# SignalsInOut.net
KiCad netlist of a schematic drawn in Altium Designer
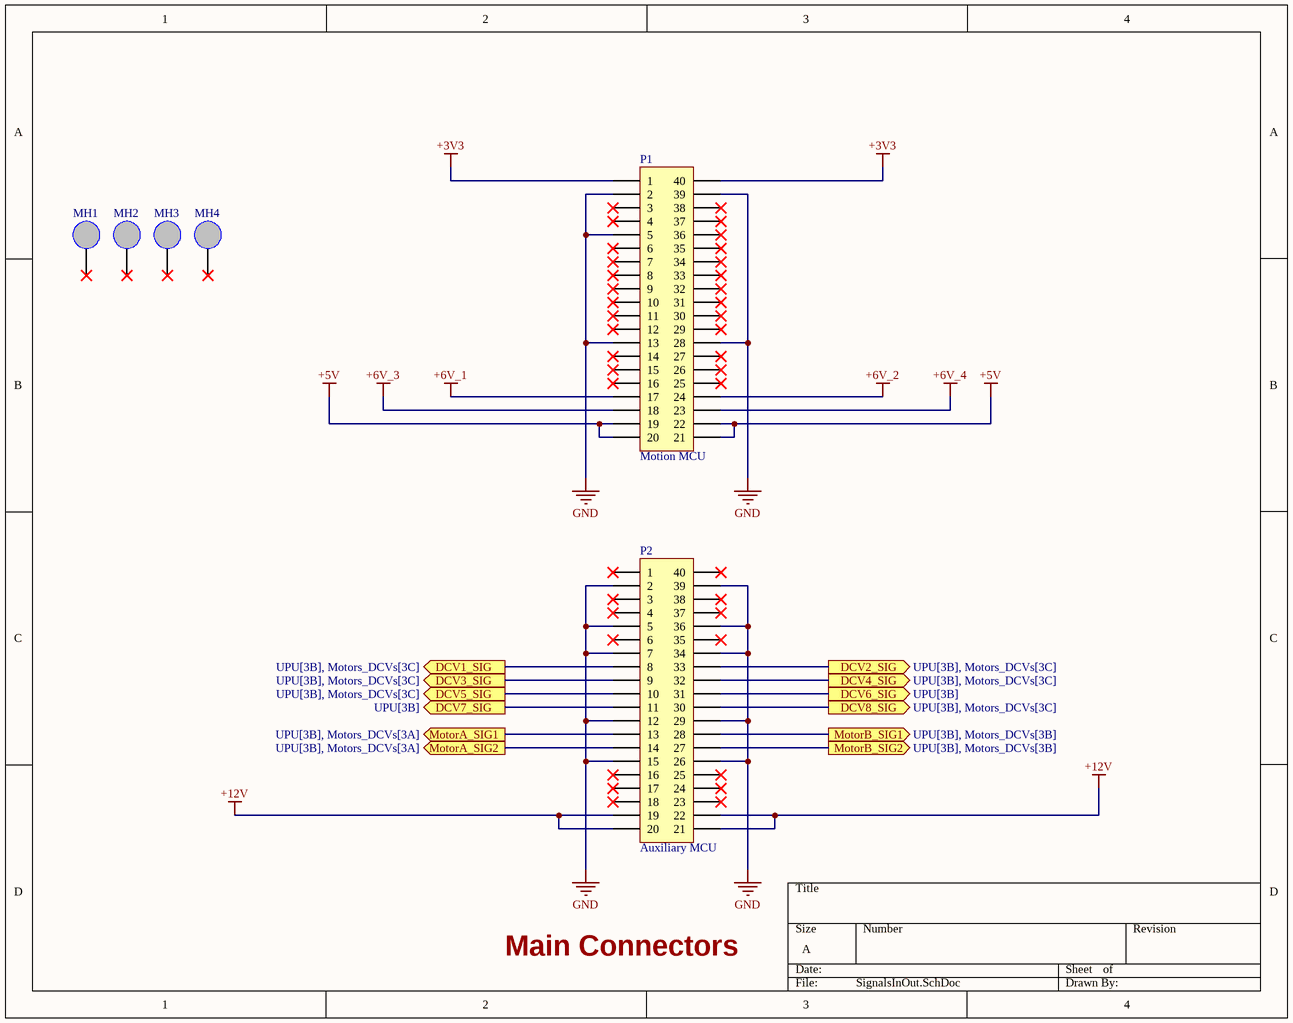
[diagram p0: SignalsInOut.SchDoc]

(export (version "E")
  (design (tool "Eeschema 10.0.6"))
  (components
    (comp (ref "MH1")
      (value "Mounting Hole 3.5mm")
      (footprint "Connector Mounting hole TH 3.5mm")
      (libsource (lib "Bypass, Testpoint and Holes") (part "Mounting Hole 3.5mm"))
    )
    (comp (ref "MH2")
      (value "Mounting Hole 3.5mm")
      (footprint "Connector Mounting hole TH 3.5mm")
      (libsource (lib "Bypass, Testpoint and Holes") (part "Mounting Hole 3.5mm"))
    )
    (comp (ref "MH3")
      (value "Mounting Hole 3.5mm")
      (footprint "Connector Mounting hole TH 3.5mm")
      (libsource (lib "Bypass, Testpoint and Holes") (part "Mounting Hole 3.5mm"))
    )
    (comp (ref "MH4")
      (value "Mounting Hole 3.5mm")
      (footprint "Connector Mounting hole TH 3.5mm")
      (libsource (lib "Bypass, Testpoint and Holes") (part "Mounting Hole 3.5mm"))
    )
    (comp (ref "P1")
      (value "Motion MCU")
      (footprint "Header F 2.54_2X20")
      (description "Header_2X20")
      (libsource (lib "Signal connectors") (part "Connector Pinheader 2x20"))
    )
    (comp (ref "P2")
      (value "Auxiliary MCU")
      (footprint "Header F 2.54_2X20")
      (description "Header_2X20")
      (libsource (lib "Signal connectors") (part "Connector Pinheader 2x20"))
    )
  )
  (nets
    (net (code "1") (name "+3V3") (class "Default")
      (node (ref "P1") (pin "1") (pinfunction "1_1") (pintype "tri_state"))
      (node (ref "P1") (pin "40") (pinfunction "40_40") (pintype "tri_state"))
    )
    (net (code "2") (name "+5V") (class "Default")
      (node (ref "P1") (pin "19") (pinfunction "19_19") (pintype "tri_state"))
      (node (ref "P1") (pin "20") (pinfunction "20_20") (pintype "tri_state"))
      (node (ref "P1") (pin "21") (pinfunction "21_21") (pintype "tri_state"))
      (node (ref "P1") (pin "22") (pinfunction "22_22") (pintype "tri_state"))
    )
    (net (code "3") (name "+6V_1") (class "Default")
      (node (ref "P1") (pin "17") (pinfunction "17_17") (pintype "tri_state"))
    )
    (net (code "4") (name "+6V_2") (class "Default")
      (node (ref "P1") (pin "24") (pinfunction "24_24") (pintype "tri_state"))
    )
    (net (code "5") (name "+6V_3") (class "Default")
      (node (ref "P1") (pin "18") (pinfunction "18_18") (pintype "tri_state"))
    )
    (net (code "6") (name "+6V_4") (class "Default")
      (node (ref "P1") (pin "23") (pinfunction "23_23") (pintype "tri_state"))
    )
    (net (code "7") (name "+12V") (class "Default")
      (node (ref "P2") (pin "19") (pinfunction "19_19") (pintype "tri_state"))
      (node (ref "P2") (pin "20") (pinfunction "20_20") (pintype "tri_state"))
      (node (ref "P2") (pin "21") (pinfunction "21_21") (pintype "tri_state"))
      (node (ref "P2") (pin "22") (pinfunction "22_22") (pintype "tri_state"))
    )
    (net (code "8") (name "/DCV1_SIG") (class "Default")
      (node (ref "P2") (pin "8") (pinfunction "8_8") (pintype "tri_state"))
    )
    (net (code "9") (name "/DCV2_SIG") (class "Default")
      (node (ref "P2") (pin "33") (pinfunction "33_33") (pintype "tri_state"))
    )
    (net (code "10") (name "/DCV3_SIG") (class "Default")
      (node (ref "P2") (pin "9") (pinfunction "9_9") (pintype "tri_state"))
    )
    (net (code "11") (name "/DCV4_SIG") (class "Default")
      (node (ref "P2") (pin "32") (pinfunction "32_32") (pintype "tri_state"))
    )
    (net (code "12") (name "/DCV5_SIG") (class "Default")
      (node (ref "P2") (pin "10") (pinfunction "10_10") (pintype "tri_state"))
    )
    (net (code "13") (name "/DCV6_SIG") (class "Default")
      (node (ref "P2") (pin "31") (pinfunction "31_31") (pintype "tri_state"))
    )
    (net (code "14") (name "/DCV7_SIG") (class "Default")
      (node (ref "P2") (pin "11") (pinfunction "11_11") (pintype "tri_state"))
    )
    (net (code "15") (name "/DCV8_SIG") (class "Default")
      (node (ref "P2") (pin "30") (pinfunction "30_30") (pintype "tri_state"))
    )
    (net (code "16") (name "/MotorA_SIG1") (class "Default")
      (node (ref "P2") (pin "13") (pinfunction "13_13") (pintype "tri_state"))
    )
    (net (code "17") (name "/MotorA_SIG2") (class "Default")
      (node (ref "P2") (pin "14") (pinfunction "14_14") (pintype "tri_state"))
    )
    (net (code "18") (name "/MotorB_SIG1") (class "Default")
      (node (ref "P2") (pin "28") (pinfunction "28_28") (pintype "tri_state"))
    )
    (net (code "19") (name "/MotorB_SIG2") (class "Default")
      (node (ref "P2") (pin "27") (pinfunction "27_27") (pintype "tri_state"))
    )
    (net (code "20") (name "GND") (class "Default")
      (node (ref "P1") (pin "13") (pinfunction "13_13") (pintype "tri_state"))
      (node (ref "P1") (pin "2") (pinfunction "2_2") (pintype "tri_state"))
      (node (ref "P1") (pin "28") (pinfunction "28_28") (pintype "tri_state"))
      (node (ref "P1") (pin "39") (pinfunction "39_39") (pintype "tri_state"))
      (node (ref "P1") (pin "5") (pinfunction "5_5") (pintype "tri_state"))
      (node (ref "P2") (pin "12") (pinfunction "12_12") (pintype "tri_state"))
      (node (ref "P2") (pin "15") (pinfunction "15_15") (pintype "tri_state"))
      (node (ref "P2") (pin "2") (pinfunction "2_2") (pintype "tri_state"))
      (node (ref "P2") (pin "26") (pinfunction "26_26") (pintype "tri_state"))
      (node (ref "P2") (pin "29") (pinfunction "29_29") (pintype "tri_state"))
      (node (ref "P2") (pin "34") (pinfunction "34_34") (pintype "tri_state"))
      (node (ref "P2") (pin "36") (pinfunction "36_36") (pintype "tri_state"))
      (node (ref "P2") (pin "39") (pinfunction "39_39") (pintype "tri_state"))
      (node (ref "P2") (pin "5") (pinfunction "5_5") (pintype "tri_state"))
      (node (ref "P2") (pin "7") (pinfunction "7_7") (pintype "tri_state"))
    )
    (net (code "21") (name "unconnected-(MH1-Pad1)") (class "Default")
      (node (ref "MH1") (pin "1") (pinfunction "1_1") (pintype "passive+no_connect"))
    )
    (net (code "22") (name "unconnected-(MH2-Pad1)") (class "Default")
      (node (ref "MH2") (pin "1") (pinfunction "1_1") (pintype "passive+no_connect"))
    )
    (net (code "23") (name "unconnected-(MH3-Pad1)") (class "Default")
      (node (ref "MH3") (pin "1") (pinfunction "1_1") (pintype "passive+no_connect"))
    )
    (net (code "24") (name "unconnected-(MH4-Pad1)") (class "Default")
      (node (ref "MH4") (pin "1") (pinfunction "1_1") (pintype "passive+no_connect"))
    )
    (net (code "25") (name "unconnected-(P1-Pad3)") (class "Default")
      (node (ref "P1") (pin "3") (pinfunction "3_3") (pintype "tri_state+no_connect"))
    )
    (net (code "26") (name "unconnected-(P1-Pad4)") (class "Default")
      (node (ref "P1") (pin "4") (pinfunction "4_4") (pintype "tri_state+no_connect"))
    )
    (net (code "27") (name "unconnected-(P1-Pad6)") (class "Default")
      (node (ref "P1") (pin "6") (pinfunction "6_6") (pintype "tri_state+no_connect"))
    )
    (net (code "28") (name "unconnected-(P1-Pad7)") (class "Default")
      (node (ref "P1") (pin "7") (pinfunction "7_7") (pintype "tri_state+no_connect"))
    )
    (net (code "29") (name "unconnected-(P1-Pad8)") (class "Default")
      (node (ref "P1") (pin "8") (pinfunction "8_8") (pintype "tri_state+no_connect"))
    )
    (net (code "30") (name "unconnected-(P1-Pad9)") (class "Default")
      (node (ref "P1") (pin "9") (pinfunction "9_9") (pintype "tri_state+no_connect"))
    )
    (net (code "31") (name "unconnected-(P1-Pad10)") (class "Default")
      (node (ref "P1") (pin "10") (pinfunction "10_10") (pintype "tri_state+no_connect"))
    )
    (net (code "32") (name "unconnected-(P1-Pad11)") (class "Default")
      (node (ref "P1") (pin "11") (pinfunction "11_11") (pintype "tri_state+no_connect"))
    )
    (net (code "33") (name "unconnected-(P1-Pad12)") (class "Default")
      (node (ref "P1") (pin "12") (pinfunction "12_12") (pintype "tri_state+no_connect"))
    )
    (net (code "34") (name "unconnected-(P1-Pad14)") (class "Default")
      (node (ref "P1") (pin "14") (pinfunction "14_14") (pintype "tri_state+no_connect"))
    )
    (net (code "35") (name "unconnected-(P1-Pad15)") (class "Default")
      (node (ref "P1") (pin "15") (pinfunction "15_15") (pintype "tri_state+no_connect"))
    )
    (net (code "36") (name "unconnected-(P1-Pad16)") (class "Default")
      (node (ref "P1") (pin "16") (pinfunction "16_16") (pintype "tri_state+no_connect"))
    )
    (net (code "37") (name "unconnected-(P1-Pad25)") (class "Default")
      (node (ref "P1") (pin "25") (pinfunction "25_25") (pintype "tri_state+no_connect"))
    )
    (net (code "38") (name "unconnected-(P1-Pad26)") (class "Default")
      (node (ref "P1") (pin "26") (pinfunction "26_26") (pintype "tri_state+no_connect"))
    )
    (net (code "39") (name "unconnected-(P1-Pad27)") (class "Default")
      (node (ref "P1") (pin "27") (pinfunction "27_27") (pintype "tri_state+no_connect"))
    )
    (net (code "40") (name "unconnected-(P1-Pad29)") (class "Default")
      (node (ref "P1") (pin "29") (pinfunction "29_29") (pintype "tri_state+no_connect"))
    )
    (net (code "41") (name "unconnected-(P1-Pad30)") (class "Default")
      (node (ref "P1") (pin "30") (pinfunction "30_30") (pintype "tri_state+no_connect"))
    )
    (net (code "42") (name "unconnected-(P1-Pad31)") (class "Default")
      (node (ref "P1") (pin "31") (pinfunction "31_31") (pintype "tri_state+no_connect"))
    )
    (net (code "43") (name "unconnected-(P1-Pad32)") (class "Default")
      (node (ref "P1") (pin "32") (pinfunction "32_32") (pintype "tri_state+no_connect"))
    )
    (net (code "44") (name "unconnected-(P1-Pad33)") (class "Default")
      (node (ref "P1") (pin "33") (pinfunction "33_33") (pintype "tri_state+no_connect"))
    )
    (net (code "45") (name "unconnected-(P1-Pad34)") (class "Default")
      (node (ref "P1") (pin "34") (pinfunction "34_34") (pintype "tri_state+no_connect"))
    )
    (net (code "46") (name "unconnected-(P1-Pad35)") (class "Default")
      (node (ref "P1") (pin "35") (pinfunction "35_35") (pintype "tri_state+no_connect"))
    )
    (net (code "47") (name "unconnected-(P1-Pad36)") (class "Default")
      (node (ref "P1") (pin "36") (pinfunction "36_36") (pintype "tri_state+no_connect"))
    )
    (net (code "48") (name "unconnected-(P1-Pad37)") (class "Default")
      (node (ref "P1") (pin "37") (pinfunction "37_37") (pintype "tri_state+no_connect"))
    )
    (net (code "49") (name "unconnected-(P1-Pad38)") (class "Default")
      (node (ref "P1") (pin "38") (pinfunction "38_38") (pintype "tri_state+no_connect"))
    )
    (net (code "50") (name "unconnected-(P2-Pad1)") (class "Default")
      (node (ref "P2") (pin "1") (pinfunction "1_1") (pintype "tri_state+no_connect"))
    )
    (net (code "51") (name "unconnected-(P2-Pad3)") (class "Default")
      (node (ref "P2") (pin "3") (pinfunction "3_3") (pintype "tri_state+no_connect"))
    )
    (net (code "52") (name "unconnected-(P2-Pad4)") (class "Default")
      (node (ref "P2") (pin "4") (pinfunction "4_4") (pintype "tri_state+no_connect"))
    )
    (net (code "53") (name "unconnected-(P2-Pad6)") (class "Default")
      (node (ref "P2") (pin "6") (pinfunction "6_6") (pintype "tri_state+no_connect"))
    )
    (net (code "54") (name "unconnected-(P2-Pad16)") (class "Default")
      (node (ref "P2") (pin "16") (pinfunction "16_16") (pintype "tri_state+no_connect"))
    )
    (net (code "55") (name "unconnected-(P2-Pad17)") (class "Default")
      (node (ref "P2") (pin "17") (pinfunction "17_17") (pintype "tri_state+no_connect"))
    )
    (net (code "56") (name "unconnected-(P2-Pad18)") (class "Default")
      (node (ref "P2") (pin "18") (pinfunction "18_18") (pintype "tri_state+no_connect"))
    )
    (net (code "57") (name "unconnected-(P2-Pad23)") (class "Default")
      (node (ref "P2") (pin "23") (pinfunction "23_23") (pintype "tri_state+no_connect"))
    )
    (net (code "58") (name "unconnected-(P2-Pad24)") (class "Default")
      (node (ref "P2") (pin "24") (pinfunction "24_24") (pintype "tri_state+no_connect"))
    )
    (net (code "59") (name "unconnected-(P2-Pad25)") (class "Default")
      (node (ref "P2") (pin "25") (pinfunction "25_25") (pintype "tri_state+no_connect"))
    )
    (net (code "60") (name "unconnected-(P2-Pad35)") (class "Default")
      (node (ref "P2") (pin "35") (pinfunction "35_35") (pintype "tri_state+no_connect"))
    )
    (net (code "61") (name "unconnected-(P2-Pad37)") (class "Default")
      (node (ref "P2") (pin "37") (pinfunction "37_37") (pintype "tri_state+no_connect"))
    )
    (net (code "62") (name "unconnected-(P2-Pad38)") (class "Default")
      (node (ref "P2") (pin "38") (pinfunction "38_38") (pintype "tri_state+no_connect"))
    )
    (net (code "63") (name "unconnected-(P2-Pad40)") (class "Default")
      (node (ref "P2") (pin "40") (pinfunction "40_40") (pintype "tri_state+no_connect"))
    )
  )
)
